# ArbPwrBoost_P8.net
KiCad netlist of a schematic drawn in Altium Designer
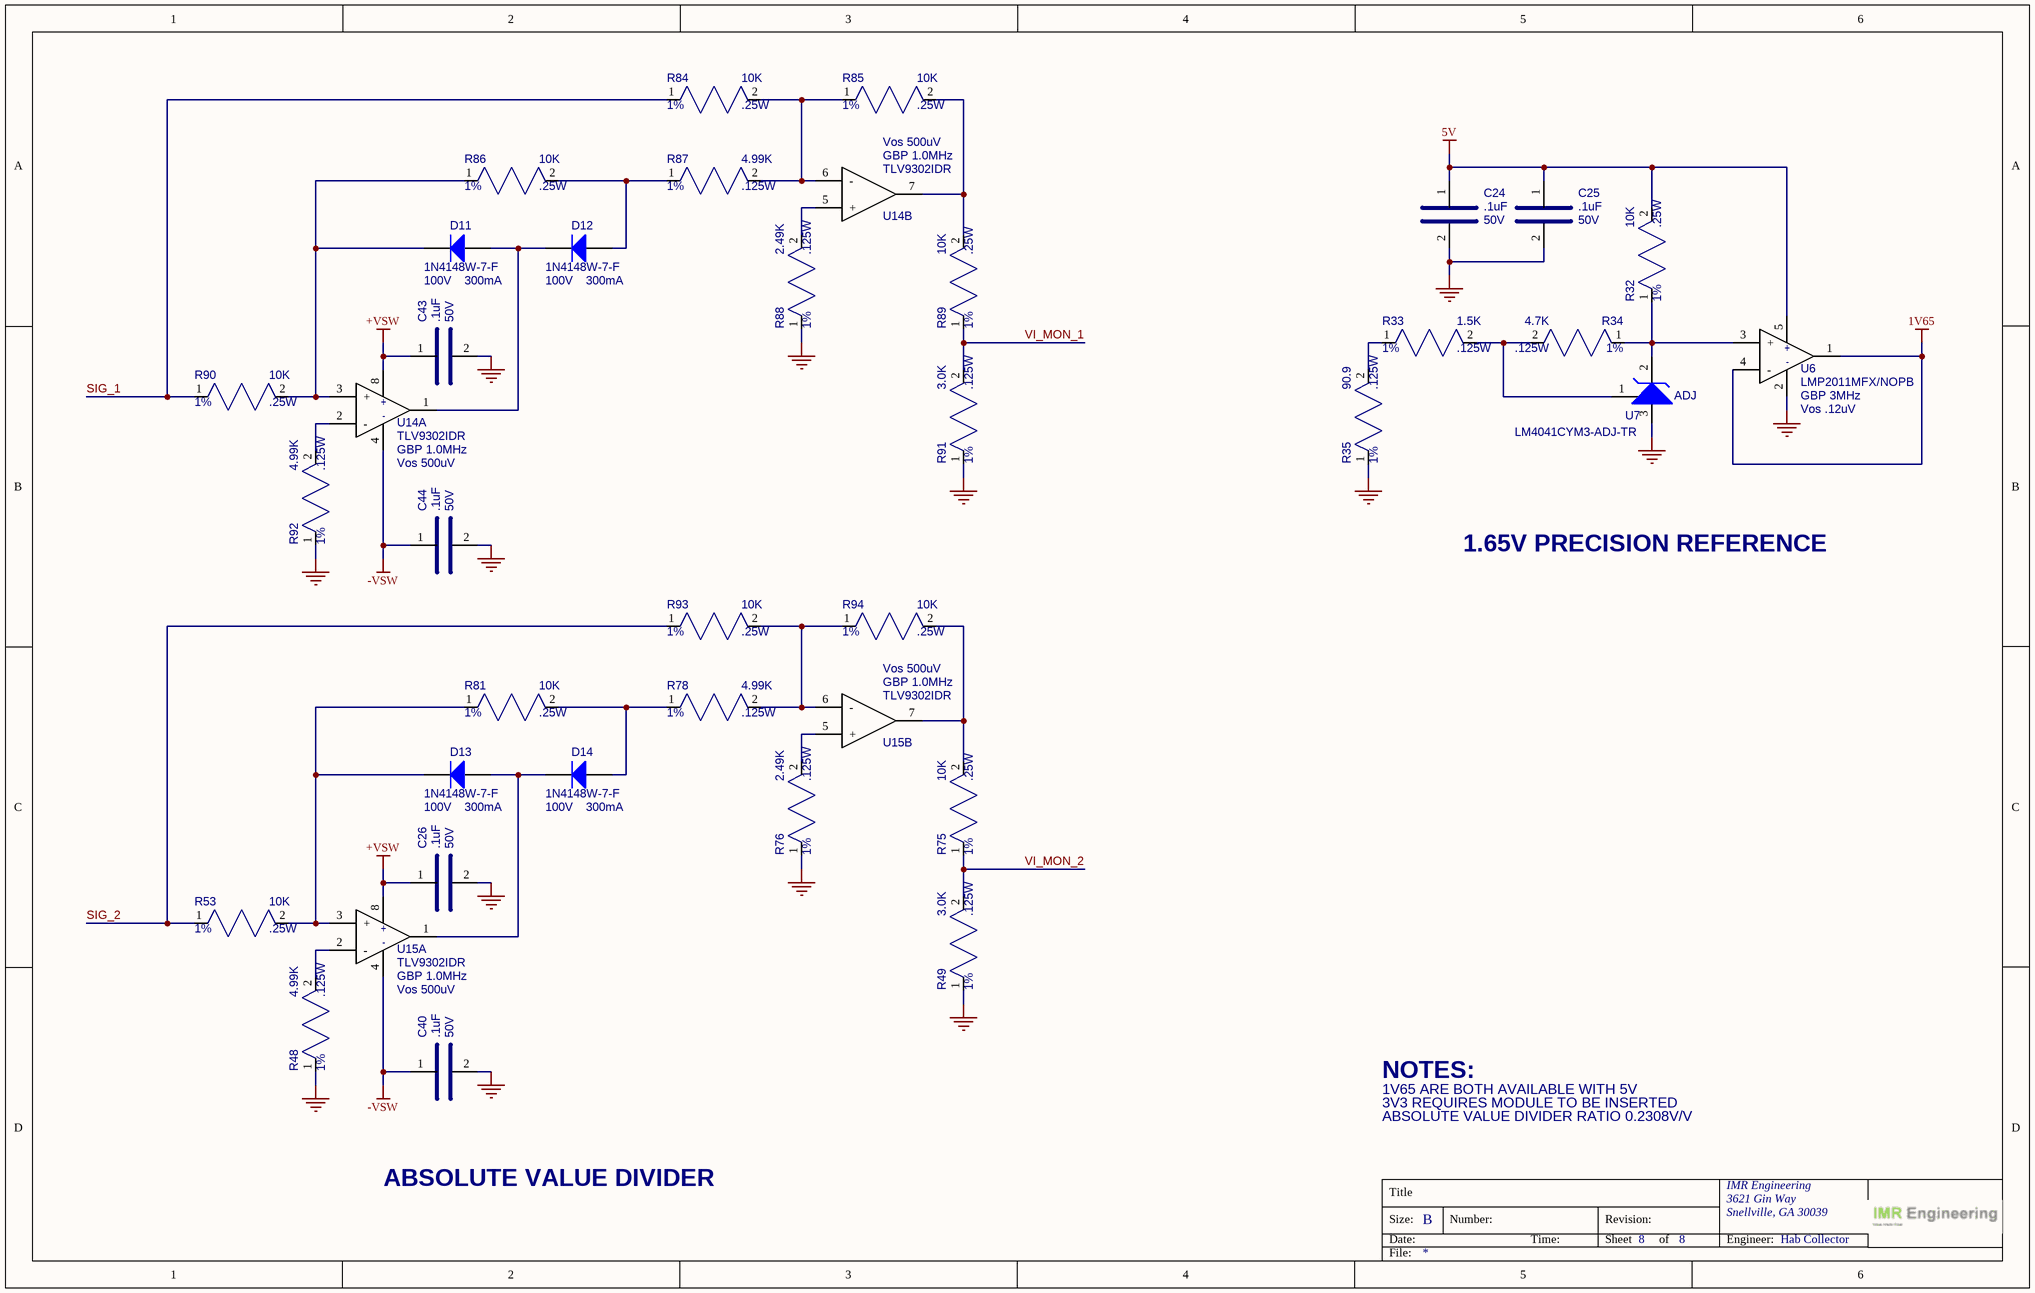
[diagram p0: ArbPwrBoost_P8.SchDoc]

(export (version "E")
  (design (tool "Eeschema 10.0.6"))
  (components
    (comp (ref "C24")
      (value ".1uF")
      (footprint "CAP_0805")
      (description "CAP CER 0.1UF 50V X7R 0805")
      (fields
        (field (name "MFG") "KYOCERA AVX")
        (field (name "VOLTAGE") "50V")
        (field (name "Comment") "KGM21NR71H104KT")
      )
      (libsource (lib "IMR_LIB_SCH_R2") (part "CAP_SMD_0.1UF_50V_0805"))
    )
    (comp (ref "C25")
      (value ".1uF")
      (footprint "CAP_0805")
      (description "CAP CER 0.1UF 50V X7R 0805")
      (fields
        (field (name "MFG") "KYOCERA AVX")
        (field (name "VOLTAGE") "50V")
        (field (name "Comment") "KGM21NR71H104KT")
      )
      (libsource (lib "IMR_LIB_SCH_R2") (part "CAP_SMD_0.1UF_50V_0805"))
    )
    (comp (ref "C26")
      (value ".1uF")
      (footprint "CAP_0805")
      (description "CAP CER 0.1UF 50V X7R 0805")
      (fields
        (field (name "MFG") "KYOCERA AVX")
        (field (name "VOLTAGE") "50V")
        (field (name "Comment") "KGM21NR71H104KT")
      )
      (libsource (lib "IMR_LIB_SCH_R2") (part "CAP_SMD_0.1UF_50V_0805"))
    )
    (comp (ref "C40")
      (value ".1uF")
      (footprint "CAP_0805")
      (description "CAP CER 0.1UF 50V X7R 0805")
      (fields
        (field (name "MFG") "KYOCERA AVX")
        (field (name "VOLTAGE") "50V")
        (field (name "Comment") "KGM21NR71H104KT")
      )
      (libsource (lib "IMR_LIB_SCH_R2") (part "CAP_SMD_0.1UF_50V_0805"))
    )
    (comp (ref "C43")
      (value ".1uF")
      (footprint "CAP_0805")
      (description "CAP CER 0.1UF 50V X7R 0805")
      (fields
        (field (name "MFG") "KYOCERA AVX")
        (field (name "VOLTAGE") "50V")
        (field (name "Comment") "KGM21NR71H104KT")
      )
      (libsource (lib "IMR_LIB_SCH_R2") (part "CAP_SMD_0.1UF_50V_0805"))
    )
    (comp (ref "C44")
      (value ".1uF")
      (footprint "CAP_0805")
      (description "CAP CER 0.1UF 50V X7R 0805")
      (fields
        (field (name "MFG") "KYOCERA AVX")
        (field (name "VOLTAGE") "50V")
        (field (name "Comment") "KGM21NR71H104KT")
      )
      (libsource (lib "IMR_LIB_SCH_R2") (part "CAP_SMD_0.1UF_50V_0805"))
    )
    (comp (ref "D11")
      (value "100V")
      (footprint "SOD123")
      (description "RELAY REED SPDT 250MA 5V")
      (fields
        (field (name "MFG") "Diodes Inc")
        (field (name "MFG_PN") "1N4148W-7-F")
        (field (name "CURRENT") "300mA")
        (field (name "Comment") "1N4148W-7-F")
      )
      (libsource (lib "IMR_LIB_SCH_R2") (part "DIODE_1N4148W-7-F"))
    )
    (comp (ref "D12")
      (value "100V")
      (footprint "SOD123")
      (description "RELAY REED SPDT 250MA 5V")
      (fields
        (field (name "MFG") "Diodes Inc")
        (field (name "MFG_PN") "1N4148W-7-F")
        (field (name "CURRENT") "300mA")
        (field (name "Comment") "1N4148W-7-F")
      )
      (libsource (lib "IMR_LIB_SCH_R2") (part "DIODE_1N4148W-7-F"))
    )
    (comp (ref "D13")
      (value "100V")
      (footprint "SOD123")
      (description "RELAY REED SPDT 250MA 5V")
      (fields
        (field (name "MFG") "Diodes Inc")
        (field (name "MFG_PN") "1N4148W-7-F")
        (field (name "CURRENT") "300mA")
        (field (name "Comment") "1N4148W-7-F")
      )
      (libsource (lib "IMR_LIB_SCH_R2") (part "DIODE_1N4148W-7-F"))
    )
    (comp (ref "D14")
      (value "100V")
      (footprint "SOD123")
      (description "RELAY REED SPDT 250MA 5V")
      (fields
        (field (name "MFG") "Diodes Inc")
        (field (name "MFG_PN") "1N4148W-7-F")
        (field (name "CURRENT") "300mA")
        (field (name "Comment") "1N4148W-7-F")
      )
      (libsource (lib "IMR_LIB_SCH_R2") (part "DIODE_1N4148W-7-F"))
    )
    (comp (ref "R32")
      (value "10K")
      (footprint "RES_0805")
      (description "RES SMD 10K OHM 1% 1/4W 0805")
      (fields
        (field (name "MFG") "Yageo")
        (field (name "POWER") ".25W")
        (field (name "TOLERANCE") "1%")
        (field (name "Comment") "RC0805FR-7W10KL")
      )
      (libsource (lib "IMR_LIB_SCH_R2") (part "RES_SMD_10K_0805_1/4W_1%"))
    )
    (comp (ref "R33")
      (value "1.5K")
      (footprint "RES_0805")
      (description "RES SMD 1.5K OHM 1% 1/8W 0805")
      (fields
        (field (name "MFG") "Yageo")
        (field (name "POWER") ".125W")
        (field (name "TOLERANCE") "1%")
        (field (name "Comment") "RC0805FR-071K5L")
      )
      (libsource (lib "IMR_LIB_SCH_R2") (part "RES_SMD_1.5K_0805_1/8W_1%"))
    )
    (comp (ref "R34")
      (value "4.7K")
      (footprint "RES_0805")
      (description "RES SMD 4.7K OHM 1% 1/8W 0805")
      (fields
        (field (name "MFG") "Yageo")
        (field (name "POWER") ".125W")
        (field (name "TOLERANCE") "1%")
        (field (name "Comment") "RC0805FR-134K7L")
      )
      (libsource (lib "IMR_LIB_SCH_R2") (part "RES_SMD_4.7K_0805_1/8W_1%"))
    )
    (comp (ref "R35")
      (value "90.9")
      (footprint "RES_0805")
      (description "RES SMD 90.9 OHM 1% 1/8W 0805")
      (fields
        (field (name "MFG") "Yageo")
        (field (name "POWER") ".125W")
        (field (name "TOLERANCE") "1%")
        (field (name "Comment") "RC0805FR-0790R9L")
      )
      (libsource (lib "IMR_LIB_SCH_R2") (part "RES_SMD_90.9_0805_1/8W_1%"))
    )
    (comp (ref "R48")
      (value "4.99K")
      (footprint "RES_0805")
      (description "RES SMD 4.99K OHM 1% 1/8W 0805")
      (fields
        (field (name "MFG") "Yageo")
        (field (name "POWER") ".125W")
        (field (name "TOLERANCE") "1%")
        (field (name "Comment") "RC0805FR-134K99L")
      )
      (libsource (lib "IMR_LIB_SCH_R2") (part "RES_SMD_4.99K_0805_1/8W_1%"))
    )
    (comp (ref "R49")
      (value "3.0K")
      (footprint "RES_0805")
      (description "RES SMD 3.0K OHM 1% 1/8W 0805")
      (fields
        (field (name "MFG") "Yageo")
        (field (name "POWER") ".125W")
        (field (name "TOLERANCE") "1%")
        (field (name "Comment") "RC0805FR-133KL")
      )
      (libsource (lib "IMR_LIB_SCH_R2") (part "RES_SMD_3.0K_0805_1/8W_1%"))
    )
    (comp (ref "R53")
      (value "10K")
      (footprint "RES_0805")
      (description "RES SMD 10K OHM 1% 1/4W 0805")
      (fields
        (field (name "MFG") "Yageo")
        (field (name "POWER") ".25W")
        (field (name "TOLERANCE") "1%")
        (field (name "Comment") "RC0805FR-7W10KL")
      )
      (libsource (lib "IMR_LIB_SCH_R2") (part "RES_SMD_10K_0805_1/4W_1%"))
    )
    (comp (ref "R75")
      (value "10K")
      (footprint "RES_0805")
      (description "RES SMD 10K OHM 1% 1/4W 0805")
      (fields
        (field (name "MFG") "Yageo")
        (field (name "POWER") ".25W")
        (field (name "TOLERANCE") "1%")
        (field (name "Comment") "RC0805FR-7W10KL")
      )
      (libsource (lib "IMR_LIB_SCH_R2") (part "RES_SMD_10K_0805_1/4W_1%"))
    )
    (comp (ref "R76")
      (value "2.49K")
      (footprint "RES_0805")
      (description "RES SMD 2.49K OHM 1% 1/8W 0805")
      (fields
        (field (name "MFG") "Yageo")
        (field (name "POWER") ".125W")
        (field (name "TOLERANCE") "1%")
        (field (name "Comment") "RC0805FR-132K49L")
      )
      (libsource (lib "IMR_LIB_SCH_R2") (part "RES_SMD_2.49K_0805_1/8W_1%"))
    )
    (comp (ref "R78")
      (value "4.99K")
      (footprint "RES_0805")
      (description "RES SMD 4.99K OHM 1% 1/8W 0805")
      (fields
        (field (name "MFG") "Yageo")
        (field (name "POWER") ".125W")
        (field (name "TOLERANCE") "1%")
        (field (name "Comment") "RC0805FR-134K99L")
      )
      (libsource (lib "IMR_LIB_SCH_R2") (part "RES_SMD_4.99K_0805_1/8W_1%"))
    )
    (comp (ref "R81")
      (value "10K")
      (footprint "RES_0805")
      (description "RES SMD 10K OHM 1% 1/4W 0805")
      (fields
        (field (name "MFG") "Yageo")
        (field (name "POWER") ".25W")
        (field (name "TOLERANCE") "1%")
        (field (name "Comment") "RC0805FR-7W10KL")
      )
      (libsource (lib "IMR_LIB_SCH_R2") (part "RES_SMD_10K_0805_1/4W_1%"))
    )
    (comp (ref "R84")
      (value "10K")
      (footprint "RES_0805")
      (description "RES SMD 10K OHM 1% 1/4W 0805")
      (fields
        (field (name "MFG") "Yageo")
        (field (name "POWER") ".25W")
        (field (name "TOLERANCE") "1%")
        (field (name "Comment") "RC0805FR-7W10KL")
      )
      (libsource (lib "IMR_LIB_SCH_R2") (part "RES_SMD_10K_0805_1/4W_1%"))
    )
    (comp (ref "R85")
      (value "10K")
      (footprint "RES_0805")
      (description "RES SMD 10K OHM 1% 1/4W 0805")
      (fields
        (field (name "MFG") "Yageo")
        (field (name "POWER") ".25W")
        (field (name "TOLERANCE") "1%")
        (field (name "Comment") "RC0805FR-7W10KL")
      )
      (libsource (lib "IMR_LIB_SCH_R2") (part "RES_SMD_10K_0805_1/4W_1%"))
    )
    (comp (ref "R86")
      (value "10K")
      (footprint "RES_0805")
      (description "RES SMD 10K OHM 1% 1/4W 0805")
      (fields
        (field (name "MFG") "Yageo")
        (field (name "POWER") ".25W")
        (field (name "TOLERANCE") "1%")
        (field (name "Comment") "RC0805FR-7W10KL")
      )
      (libsource (lib "IMR_LIB_SCH_R2") (part "RES_SMD_10K_0805_1/4W_1%"))
    )
    (comp (ref "R87")
      (value "4.99K")
      (footprint "RES_0805")
      (description "RES SMD 4.99K OHM 1% 1/8W 0805")
      (fields
        (field (name "MFG") "Yageo")
        (field (name "POWER") ".125W")
        (field (name "TOLERANCE") "1%")
        (field (name "Comment") "RC0805FR-134K99L")
      )
      (libsource (lib "IMR_LIB_SCH_R2") (part "RES_SMD_4.99K_0805_1/8W_1%"))
    )
    (comp (ref "R88")
      (value "2.49K")
      (footprint "RES_0805")
      (description "RES SMD 2.49K OHM 1% 1/8W 0805")
      (fields
        (field (name "MFG") "Yageo")
        (field (name "POWER") ".125W")
        (field (name "TOLERANCE") "1%")
        (field (name "Comment") "RC0805FR-132K49L")
      )
      (libsource (lib "IMR_LIB_SCH_R2") (part "RES_SMD_2.49K_0805_1/8W_1%"))
    )
    (comp (ref "R89")
      (value "10K")
      (footprint "RES_0805")
      (description "RES SMD 10K OHM 1% 1/4W 0805")
      (fields
        (field (name "MFG") "Yageo")
        (field (name "POWER") ".25W")
        (field (name "TOLERANCE") "1%")
        (field (name "Comment") "RC0805FR-7W10KL")
      )
      (libsource (lib "IMR_LIB_SCH_R2") (part "RES_SMD_10K_0805_1/4W_1%"))
    )
    (comp (ref "R90")
      (value "10K")
      (footprint "RES_0805")
      (description "RES SMD 10K OHM 1% 1/4W 0805")
      (fields
        (field (name "MFG") "Yageo")
        (field (name "POWER") ".25W")
        (field (name "TOLERANCE") "1%")
        (field (name "Comment") "RC0805FR-7W10KL")
      )
      (libsource (lib "IMR_LIB_SCH_R2") (part "RES_SMD_10K_0805_1/4W_1%"))
    )
    (comp (ref "R91")
      (value "3.0K")
      (footprint "RES_0805")
      (description "RES SMD 3.0K OHM 1% 1/8W 0805")
      (fields
        (field (name "MFG") "Yageo")
        (field (name "POWER") ".125W")
        (field (name "TOLERANCE") "1%")
        (field (name "Comment") "RC0805FR-133KL")
      )
      (libsource (lib "IMR_LIB_SCH_R2") (part "RES_SMD_3.0K_0805_1/8W_1%"))
    )
    (comp (ref "R92")
      (value "4.99K")
      (footprint "RES_0805")
      (description "RES SMD 4.99K OHM 1% 1/8W 0805")
      (fields
        (field (name "MFG") "Yageo")
        (field (name "POWER") ".125W")
        (field (name "TOLERANCE") "1%")
        (field (name "Comment") "RC0805FR-134K99L")
      )
      (libsource (lib "IMR_LIB_SCH_R2") (part "RES_SMD_4.99K_0805_1/8W_1%"))
    )
    (comp (ref "R93")
      (value "10K")
      (footprint "RES_0805")
      (description "RES SMD 10K OHM 1% 1/4W 0805")
      (fields
        (field (name "MFG") "Yageo")
        (field (name "POWER") ".25W")
        (field (name "TOLERANCE") "1%")
        (field (name "Comment") "RC0805FR-7W10KL")
      )
      (libsource (lib "IMR_LIB_SCH_R2") (part "RES_SMD_10K_0805_1/4W_1%"))
    )
    (comp (ref "R94")
      (value "10K")
      (footprint "RES_0805")
      (description "RES SMD 10K OHM 1% 1/4W 0805")
      (fields
        (field (name "MFG") "Yageo")
        (field (name "POWER") ".25W")
        (field (name "TOLERANCE") "1%")
        (field (name "Comment") "RC0805FR-7W10KL")
      )
      (libsource (lib "IMR_LIB_SCH_R2") (part "RES_SMD_10K_0805_1/4W_1%"))
    )
    (comp (ref "U6")
      (value "GBP 3MHz")
      (footprint "SOT-23-5")
      (description "IC OPAMP GP 3MHZ .12uV CIRCUIT SOT23-5")
      (fields
        (field (name "MFG") "Texas Instruments")
        (field (name "MFG_PN") "LMP2011MFX/NOPB")
        (field (name "VOS") "Vos .12uV")
        (field (name "Comment") "LMP2011MFX/NOPB")
      )
      (libsource (lib "IMR_LIB_SCH_R2") (part "OPAMP_LMP2011MFX/NOPB"))
    )
    (comp (ref "U7")
      (value "ADJ")
      (footprint "SOT-23")
      (description "IC VREF SHUNT ADJ 0.5% SOT23-3")
      (fields
        (field (name "MFG") "Microchip")
        (field (name "MFG_PN") "LM4041CYM3-ADJ-TR")
        (field (name "Comment") "LM4041CYM3-ADJ-TR")
      )
      (libsource (lib "IMR_LIB_SCH_R2") (part "IC_LM4041CYM3-ADJ-TR"))
    )
    (comp (ref "U14")
      (value "GBP 1.0MHz")
      (footprint "SOIC-8_49")
      (description "IC OPAMP GP 2 CIRCUIT 8SOIC")
      (fields
        (field (name "MFG") "Texas Instruments")
        (field (name "MFG_PN") "TLV9302IDR")
        (field (name "VOS") "Vos 500uV")
        (field (name "Comment") "TLV9302IDR")
      )
      (libsource (lib "IMR_LIB_SCH_R2") (part "OPAMP_TLV9302IDR"))
    )
    (comp (ref "U15")
      (value "GBP 1.0MHz")
      (footprint "SOIC-8_49")
      (description "IC OPAMP GP 2 CIRCUIT 8SOIC")
      (fields
        (field (name "MFG") "Texas Instruments")
        (field (name "MFG_PN") "TLV9302IDR")
        (field (name "VOS") "Vos 500uV")
        (field (name "Comment") "TLV9302IDR")
      )
      (libsource (lib "IMR_LIB_SCH_R2") (part "OPAMP_TLV9302IDR"))
    )
  )
  (nets
    (net (code "1") (name "+VSW") (class "Default")
      (node (ref "C26") (pin "1") (pinfunction "1_1") (pintype "passive"))
      (node (ref "C43") (pin "1") (pinfunction "1_1") (pintype "passive"))
      (node (ref "U14") (pin "8") (pintype "passive"))
      (node (ref "U15") (pin "8") (pintype "passive"))
    )
    (net (code "2") (name "-VSW") (class "Default")
      (node (ref "C40") (pin "1") (pinfunction "1_1") (pintype "passive"))
      (node (ref "C44") (pin "1") (pinfunction "1_1") (pintype "passive"))
      (node (ref "U14") (pin "4") (pintype "passive"))
      (node (ref "U15") (pin "4") (pintype "passive"))
    )
    (net (code "3") (name "/SIG_1") (class "Default")
      (node (ref "R84") (pin "1") (pinfunction "1_1") (pintype "passive"))
      (node (ref "R90") (pin "1") (pinfunction "1_1") (pintype "passive"))
    )
    (net (code "4") (name "/SIG_2") (class "Default")
      (node (ref "R53") (pin "1") (pinfunction "1_1") (pintype "passive"))
      (node (ref "R93") (pin "1") (pinfunction "1_1") (pintype "passive"))
    )
    (net (code "5") (name "/VI_MON_1") (class "Default")
      (node (ref "R89") (pin "1") (pinfunction "1_1") (pintype "passive"))
      (node (ref "R91") (pin "2") (pinfunction "2_2") (pintype "passive"))
    )
    (net (code "6") (name "/VI_MON_2") (class "Default")
      (node (ref "R49") (pin "2") (pinfunction "2_2") (pintype "passive"))
      (node (ref "R75") (pin "1") (pinfunction "1_1") (pintype "passive"))
    )
    (net (code "7") (name "1V65") (class "Default")
      (node (ref "U6") (pin "1") (pintype "passive"))
      (node (ref "U6") (pin "4") (pinfunction "-_4") (pintype "passive"))
    )
    (net (code "8") (name "5V") (class "Default")
      (node (ref "C24") (pin "1") (pinfunction "1_1") (pintype "passive"))
      (node (ref "C25") (pin "1") (pinfunction "1_1") (pintype "passive"))
      (node (ref "R32") (pin "2") (pinfunction "2_2") (pintype "passive"))
      (node (ref "U6") (pin "5") (pintype "passive"))
    )
    (net (code "9") (name "GND") (class "Default")
      (node (ref "C24") (pin "2") (pinfunction "2_2") (pintype "passive"))
      (node (ref "C25") (pin "2") (pinfunction "2_2") (pintype "passive"))
      (node (ref "C26") (pin "2") (pinfunction "2_2") (pintype "passive"))
      (node (ref "C40") (pin "2") (pinfunction "2_2") (pintype "passive"))
      (node (ref "C43") (pin "2") (pinfunction "2_2") (pintype "passive"))
      (node (ref "C44") (pin "2") (pinfunction "2_2") (pintype "passive"))
      (node (ref "R35") (pin "1") (pinfunction "1_1") (pintype "passive"))
      (node (ref "R48") (pin "1") (pinfunction "1_1") (pintype "passive"))
      (node (ref "R49") (pin "1") (pinfunction "1_1") (pintype "passive"))
      (node (ref "R76") (pin "1") (pinfunction "1_1") (pintype "passive"))
      (node (ref "R88") (pin "1") (pinfunction "1_1") (pintype "passive"))
      (node (ref "R91") (pin "1") (pinfunction "1_1") (pintype "passive"))
      (node (ref "R92") (pin "1") (pinfunction "1_1") (pintype "passive"))
      (node (ref "U6") (pin "2") (pintype "passive"))
      (node (ref "U7") (pin "3") (pinfunction "A_3") (pintype "passive"))
    )
    (net (code "10") (name "Net-(D11-A)") (class "Default")
      (node (ref "D11") (pin "1") (pinfunction "A_1") (pintype "passive"))
      (node (ref "D12") (pin "2") (pinfunction "K_2") (pintype "passive"))
      (node (ref "U14") (pin "1") (pintype "passive"))
    )
    (net (code "11") (name "Net-(D11-K)") (class "Default")
      (node (ref "D11") (pin "2") (pinfunction "K_2") (pintype "passive"))
      (node (ref "R86") (pin "1") (pinfunction "1_1") (pintype "passive"))
      (node (ref "R90") (pin "2") (pinfunction "2_2") (pintype "passive"))
      (node (ref "U14") (pin "3") (pinfunction "+_3") (pintype "passive"))
    )
    (net (code "12") (name "Net-(D12-A)") (class "Default")
      (node (ref "D12") (pin "1") (pinfunction "A_1") (pintype "passive"))
      (node (ref "R86") (pin "2") (pinfunction "2_2") (pintype "passive"))
      (node (ref "R87") (pin "1") (pinfunction "1_1") (pintype "passive"))
    )
    (net (code "13") (name "Net-(D13-A)") (class "Default")
      (node (ref "D13") (pin "1") (pinfunction "A_1") (pintype "passive"))
      (node (ref "D14") (pin "2") (pinfunction "K_2") (pintype "passive"))
      (node (ref "U15") (pin "1") (pintype "passive"))
    )
    (net (code "14") (name "Net-(D13-K)") (class "Default")
      (node (ref "D13") (pin "2") (pinfunction "K_2") (pintype "passive"))
      (node (ref "R53") (pin "2") (pinfunction "2_2") (pintype "passive"))
      (node (ref "R81") (pin "1") (pinfunction "1_1") (pintype "passive"))
      (node (ref "U15") (pin "3") (pinfunction "+_3") (pintype "passive"))
    )
    (net (code "15") (name "Net-(D14-A)") (class "Default")
      (node (ref "D14") (pin "1") (pinfunction "A_1") (pintype "passive"))
      (node (ref "R78") (pin "1") (pinfunction "1_1") (pintype "passive"))
      (node (ref "R81") (pin "2") (pinfunction "2_2") (pintype "passive"))
    )
    (net (code "16") (name "Net-(R33-Pad1)") (class "Default")
      (node (ref "R33") (pin "1") (pinfunction "1_1") (pintype "passive"))
      (node (ref "R35") (pin "2") (pinfunction "2_2") (pintype "passive"))
    )
    (net (code "17") (name "Net-(R75-Pad2)") (class "Default")
      (node (ref "R75") (pin "2") (pinfunction "2_2") (pintype "passive"))
      (node (ref "R94") (pin "2") (pinfunction "2_2") (pintype "passive"))
      (node (ref "U15") (pin "7") (pintype "passive"))
    )
    (net (code "18") (name "Net-(R85-Pad2)") (class "Default")
      (node (ref "R85") (pin "2") (pinfunction "2_2") (pintype "passive"))
      (node (ref "R89") (pin "2") (pinfunction "2_2") (pintype "passive"))
      (node (ref "U14") (pin "7") (pintype "passive"))
    )
    (net (code "19") (name "Net-(U6-+)") (class "Default")
      (node (ref "R32") (pin "1") (pinfunction "1_1") (pintype "passive"))
      (node (ref "R34") (pin "1") (pinfunction "1_1") (pintype "passive"))
      (node (ref "U6") (pin "3") (pinfunction "+_3") (pintype "passive"))
      (node (ref "U7") (pin "2") (pinfunction "K_2") (pintype "passive"))
    )
    (net (code "20") (name "Net-(U7-FB)") (class "Default")
      (node (ref "R33") (pin "2") (pinfunction "2_2") (pintype "passive"))
      (node (ref "R34") (pin "2") (pinfunction "2_2") (pintype "passive"))
      (node (ref "U7") (pin "1") (pinfunction "FB_1") (pintype "passive"))
    )
    (net (code "21") (name "Net-(U14A--)") (class "Default")
      (node (ref "R92") (pin "2") (pinfunction "2_2") (pintype "passive"))
      (node (ref "U14") (pin "2") (pinfunction "-_2") (pintype "passive"))
    )
    (net (code "22") (name "Net-(U14B-+)") (class "Default")
      (node (ref "R88") (pin "2") (pinfunction "2_2") (pintype "passive"))
      (node (ref "U14") (pin "5") (pinfunction "+_5") (pintype "passive"))
    )
    (net (code "23") (name "Net-(U14B--)") (class "Default")
      (node (ref "R84") (pin "2") (pinfunction "2_2") (pintype "passive"))
      (node (ref "R85") (pin "1") (pinfunction "1_1") (pintype "passive"))
      (node (ref "R87") (pin "2") (pinfunction "2_2") (pintype "passive"))
      (node (ref "U14") (pin "6") (pinfunction "-_6") (pintype "passive"))
    )
    (net (code "24") (name "Net-(U15A--)") (class "Default")
      (node (ref "R48") (pin "2") (pinfunction "2_2") (pintype "passive"))
      (node (ref "U15") (pin "2") (pinfunction "-_2") (pintype "passive"))
    )
    (net (code "25") (name "Net-(U15B-+)") (class "Default")
      (node (ref "R76") (pin "2") (pinfunction "2_2") (pintype "passive"))
      (node (ref "U15") (pin "5") (pinfunction "+_5") (pintype "passive"))
    )
    (net (code "26") (name "Net-(U15B--)") (class "Default")
      (node (ref "R78") (pin "2") (pinfunction "2_2") (pintype "passive"))
      (node (ref "R93") (pin "2") (pinfunction "2_2") (pintype "passive"))
      (node (ref "R94") (pin "1") (pinfunction "1_1") (pintype "passive"))
      (node (ref "U15") (pin "6") (pinfunction "-_6") (pintype "passive"))
    )
  )
)
